# pluto-camera-trigger-shield.net
KiCad netlist of a schematic drawn in EAGLE
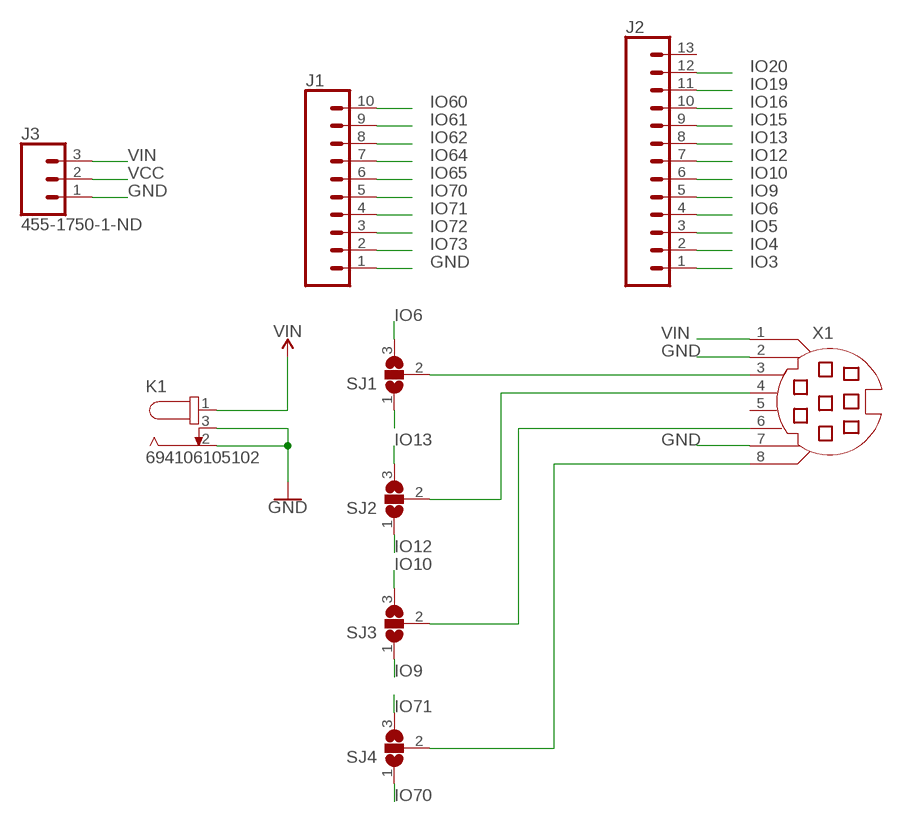
[diagram p0: schematic, sheet 1]

(export (version "E")
  (design (tool "Eeschema 10.0.6"))
  (components
    (comp (ref "J1")
      (value "CONN_10\"")
      (footprint "eagle-import:1X10")
      (libsource (lib "eagle-import") (part "CONN_10{dblquote}"))
    )
    (comp (ref "J2")
      (value "CONN_13")
      (footprint "eagle-import:1X13")
      (libsource (lib "eagle-import") (part "CONN_13"))
    )
    (comp (ref "J3")
      (value "455-1750-1-ND")
      (footprint "eagle-import:1X03")
      (libsource (lib "eagle-import") (part "CONN_03"))
    )
    (comp (ref "K1")
      (value "694106105102")
      (footprint "eagle-import:694106105102")
      (libsource (lib "eagle-import") (part "694106105102"))
    )
    (comp (ref "SJ1")
      (value "SJ2W")
      (footprint "eagle-import:SJ_2")
      (libsource (lib "eagle-import") (part "SJ2W"))
    )
    (comp (ref "SJ2")
      (value "SJ2W")
      (footprint "eagle-import:SJ_2")
      (libsource (lib "eagle-import") (part "SJ2W"))
    )
    (comp (ref "SJ3")
      (value "SJ2W")
      (footprint "eagle-import:SJ_2")
      (libsource (lib "eagle-import") (part "SJ2W"))
    )
    (comp (ref "SJ4")
      (value "SJ2W")
      (footprint "eagle-import:SJ_2")
      (libsource (lib "eagle-import") (part "SJ2W"))
    )
    (comp (ref "X1")
      (value "MD08SS")
      (footprint "eagle-import:MDIN08SS")
      (libsource (lib "eagle-import") (part "MD08SS"))
    )
  )
  (nets
    (net (code "1") (name "/IO3") (class "Default")
      (node (ref "J2") (pin "1") (pinfunction "1_1") (pintype "passive"))
    )
    (net (code "2") (name "/IO4") (class "Default")
      (node (ref "J2") (pin "2") (pinfunction "2_2") (pintype "passive"))
    )
    (net (code "3") (name "/IO5") (class "Default")
      (node (ref "J2") (pin "3") (pinfunction "3_3") (pintype "passive"))
      (node (ref "SJ1") (pin "1") (pinfunction "1_1") (pintype "passive"))
    )
    (net (code "4") (name "/IO6") (class "Default")
      (node (ref "J2") (pin "4") (pinfunction "4_4") (pintype "passive"))
      (node (ref "SJ1") (pin "3") (pinfunction "3_3") (pintype "passive"))
    )
    (net (code "5") (name "/IO9") (class "Default")
      (node (ref "J2") (pin "5") (pinfunction "5_5") (pintype "passive"))
      (node (ref "SJ3") (pin "1") (pinfunction "1_1") (pintype "passive"))
    )
    (net (code "6") (name "/IO10") (class "Default")
      (node (ref "J2") (pin "6") (pinfunction "6_6") (pintype "passive"))
      (node (ref "SJ3") (pin "3") (pinfunction "3_3") (pintype "passive"))
    )
    (net (code "7") (name "/IO12") (class "Default")
      (node (ref "J2") (pin "7") (pinfunction "7_7") (pintype "passive"))
      (node (ref "SJ2") (pin "1") (pinfunction "1_1") (pintype "passive"))
    )
    (net (code "8") (name "/IO13") (class "Default")
      (node (ref "J2") (pin "8") (pinfunction "8_8") (pintype "passive"))
      (node (ref "SJ2") (pin "3") (pinfunction "3_3") (pintype "passive"))
    )
    (net (code "9") (name "/IO15") (class "Default")
      (node (ref "J2") (pin "9") (pinfunction "9_9") (pintype "passive"))
    )
    (net (code "10") (name "/IO16") (class "Default")
      (node (ref "J2") (pin "10") (pinfunction "10_10") (pintype "passive"))
    )
    (net (code "11") (name "/IO19") (class "Default")
      (node (ref "J2") (pin "11") (pinfunction "11_11") (pintype "passive"))
    )
    (net (code "12") (name "/IO20") (class "Default")
      (node (ref "J2") (pin "12") (pinfunction "12_12") (pintype "passive"))
    )
    (net (code "13") (name "/IO60") (class "Default")
      (node (ref "J1") (pin "10") (pinfunction "10_10") (pintype "passive"))
    )
    (net (code "14") (name "/IO61") (class "Default")
      (node (ref "J1") (pin "9") (pinfunction "9_9") (pintype "passive"))
    )
    (net (code "15") (name "/IO62") (class "Default")
      (node (ref "J1") (pin "8") (pinfunction "8_8") (pintype "passive"))
    )
    (net (code "16") (name "/IO64") (class "Default")
      (node (ref "J1") (pin "7") (pinfunction "7_7") (pintype "passive"))
    )
    (net (code "17") (name "/IO65") (class "Default")
      (node (ref "J1") (pin "6") (pinfunction "6_6") (pintype "passive"))
    )
    (net (code "18") (name "/IO70") (class "Default")
      (node (ref "J1") (pin "5") (pinfunction "5_5") (pintype "passive"))
      (node (ref "SJ4") (pin "1") (pinfunction "1_1") (pintype "passive"))
    )
    (net (code "19") (name "/IO71") (class "Default")
      (node (ref "J1") (pin "4") (pinfunction "4_4") (pintype "passive"))
      (node (ref "SJ4") (pin "3") (pinfunction "3_3") (pintype "passive"))
    )
    (net (code "20") (name "/IO72") (class "Default")
      (node (ref "J1") (pin "3") (pinfunction "3_3") (pintype "passive"))
    )
    (net (code "21") (name "/IO73") (class "Default")
      (node (ref "J1") (pin "2") (pinfunction "2_2") (pintype "passive"))
    )
    (net (code "22") (name "/VCC") (class "Default")
      (node (ref "J3") (pin "2") (pinfunction "2_2") (pintype "passive"))
    )
    (net (code "23") (name "GND") (class "Default")
      (node (ref "J1") (pin "1") (pinfunction "1_1") (pintype "passive"))
      (node (ref "J3") (pin "1") (pinfunction "1_1") (pintype "passive"))
      (node (ref "K1") (pin "2") (pinfunction "2_2") (pintype "passive"))
      (node (ref "K1") (pin "3") (pinfunction "3_3") (pintype "passive"))
      (node (ref "X1") (pin "2") (pinfunction "2_2") (pintype "passive"))
      (node (ref "X1") (pin "7") (pinfunction "7_7") (pintype "passive"))
    )
    (net (code "24") (name "Net-(SJ1-Pad2)") (class "Default")
      (node (ref "SJ1") (pin "2") (pinfunction "2_2") (pintype "passive"))
      (node (ref "X1") (pin "3") (pinfunction "3_3") (pintype "passive"))
    )
    (net (code "25") (name "Net-(SJ2-Pad2)") (class "Default")
      (node (ref "SJ2") (pin "2") (pinfunction "2_2") (pintype "passive"))
      (node (ref "X1") (pin "4") (pinfunction "4_4") (pintype "passive"))
    )
    (net (code "26") (name "Net-(SJ3-Pad2)") (class "Default")
      (node (ref "SJ3") (pin "2") (pinfunction "2_2") (pintype "passive"))
      (node (ref "X1") (pin "6") (pinfunction "6_6") (pintype "passive"))
    )
    (net (code "27") (name "Net-(SJ4-Pad2)") (class "Default")
      (node (ref "SJ4") (pin "2") (pinfunction "2_2") (pintype "passive"))
      (node (ref "X1") (pin "8") (pinfunction "8_8") (pintype "passive"))
    )
    (net (code "28") (name "VIN") (class "Default")
      (node (ref "J3") (pin "3") (pinfunction "3_3") (pintype "passive"))
      (node (ref "K1") (pin "1") (pinfunction "1_1") (pintype "passive"))
      (node (ref "X1") (pin "1") (pinfunction "1_1") (pintype "passive"))
    )
    (net (code "29") (name "unconnected-(J2-Pad13)") (class "Default")
      (node (ref "J2") (pin "13") (pinfunction "13_13") (pintype "passive"))
    )
    (net (code "30") (name "unconnected-(X1-Pad5)") (class "Default")
      (node (ref "X1") (pin "5") (pinfunction "5_5") (pintype "passive"))
    )
  )
)
